# gt-jtx-2560.net
KiCad netlist of a schematic drawn in EAGLE
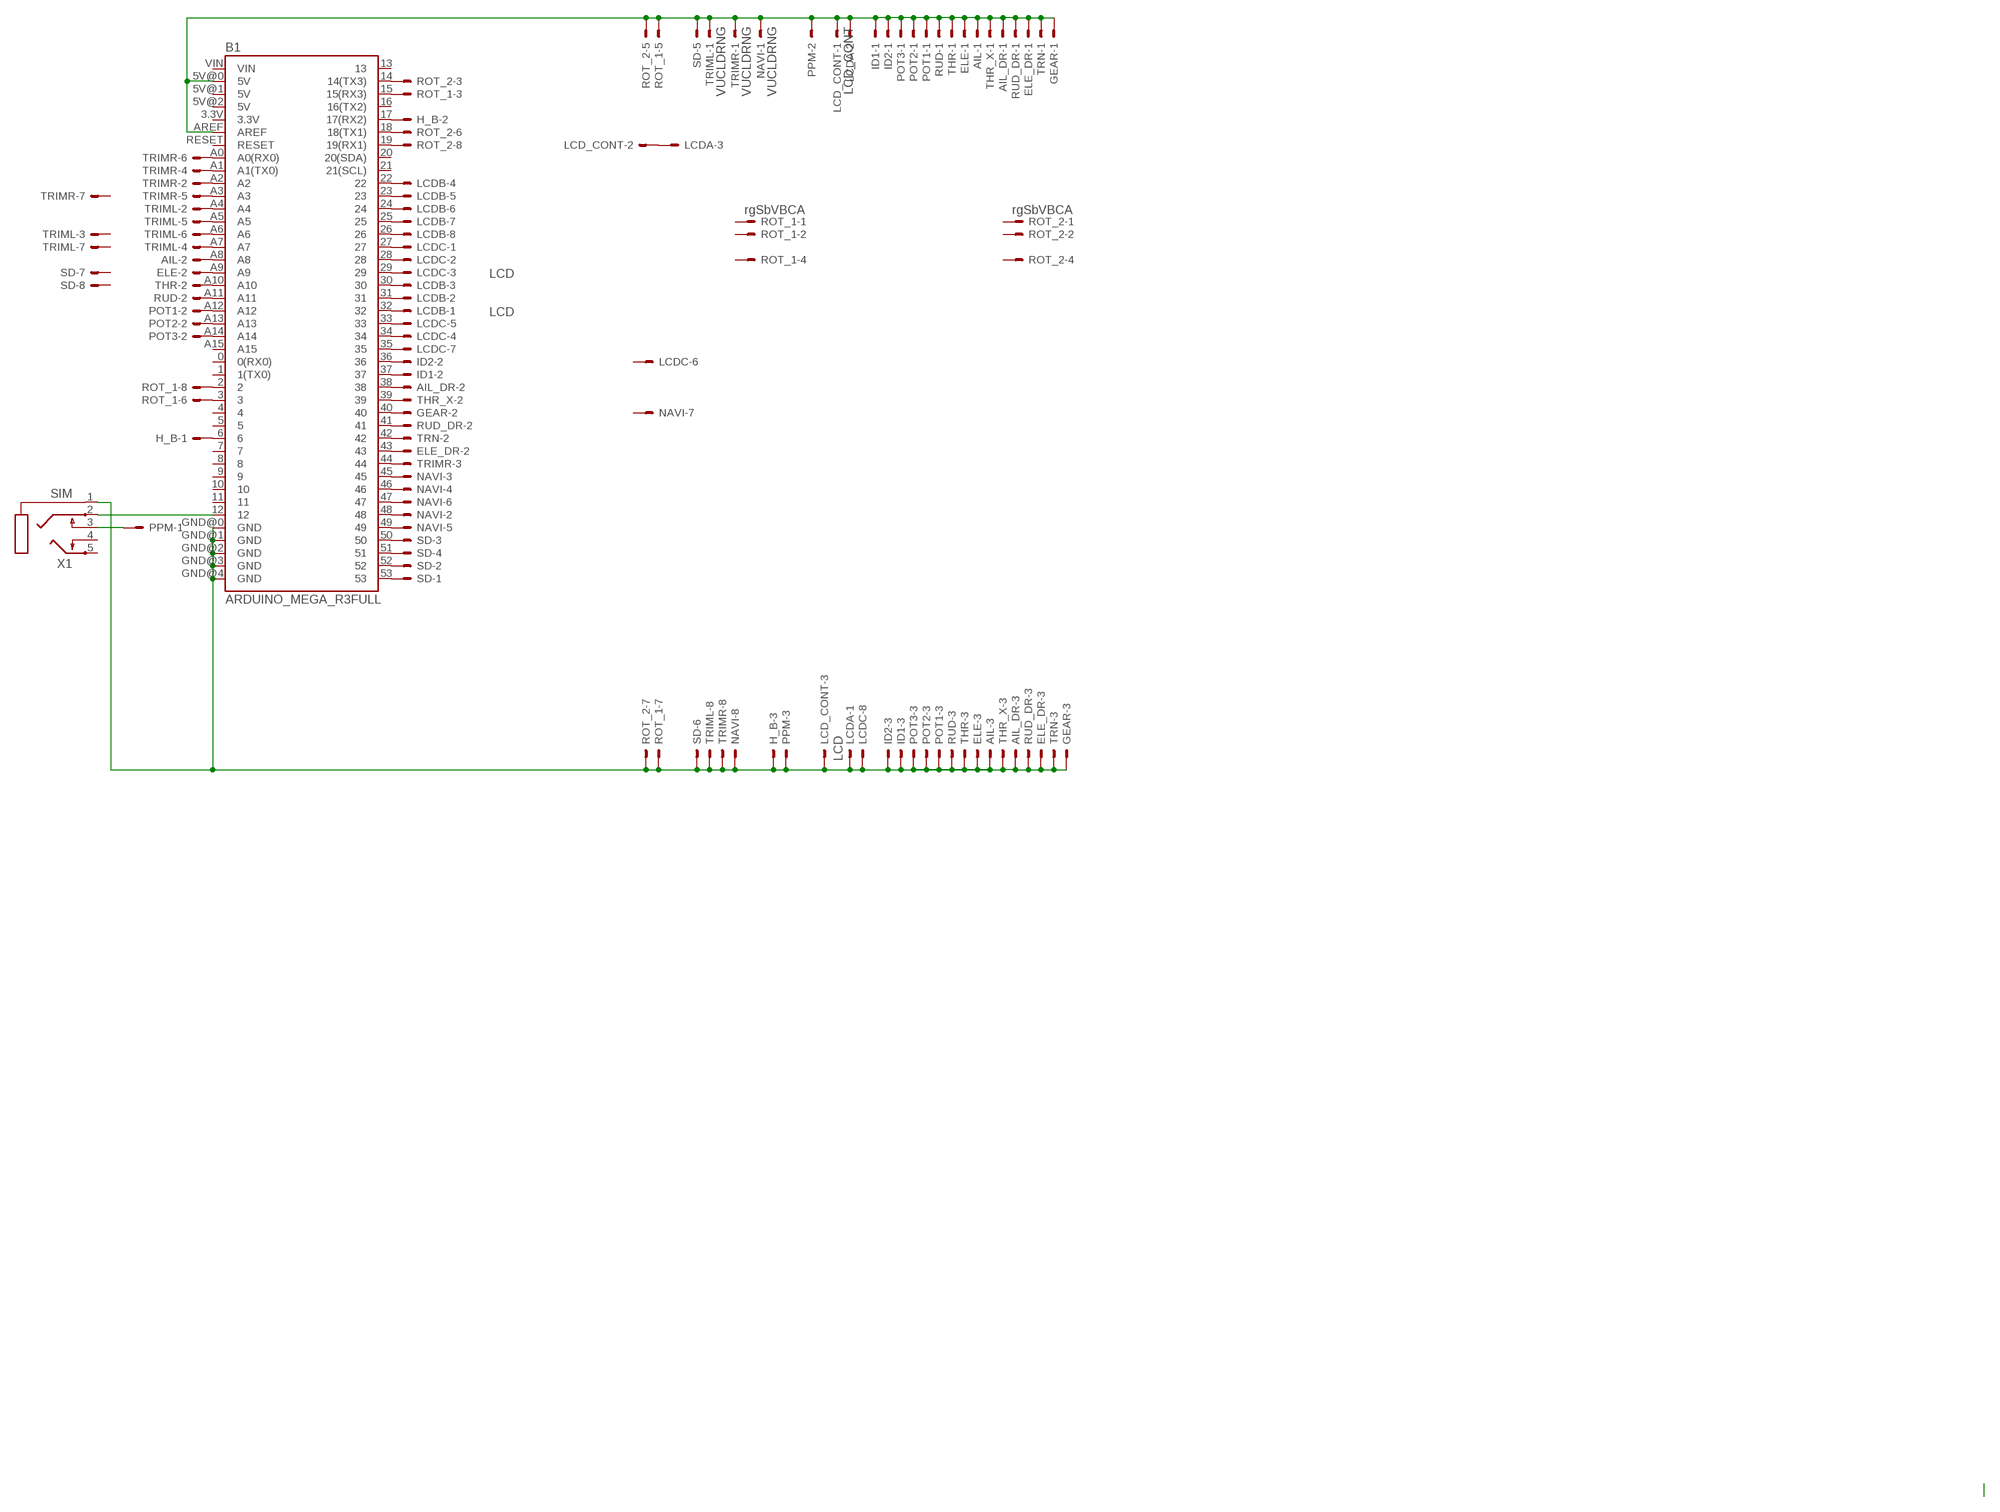
[diagram p0: schematic, sheet 1]

(export (version "E")
  (design (tool "Eeschema 10.0.6"))
  (components
    (comp (ref "AIL")
      (value "JST-XH-03-PIN-LONG-PAD")
      (footprint "eagle-import:JST-XH-03-PACKAGE-LONG-PAD")
      (libsource (lib "eagle-import") (part "JST-XH-03-PIN-LONG-PAD"))
    )
    (comp (ref "AIL_DR")
      (value "JST-XH-03-PIN-LONG-PAD")
      (footprint "eagle-import:JST-XH-03-PACKAGE-LONG-PAD")
      (libsource (lib "eagle-import") (part "JST-XH-03-PIN-LONG-PAD"))
    )
    (comp (ref "B1")
      (value "ARDUINO_MEGA_R3FULL")
      (footprint "eagle-import:ARDUINO_MEGA")
      (libsource (lib "eagle-import") (part "ARDUINO_MEGA_R3FULL"))
    )
    (comp (ref "ELE")
      (value "JST-XH-03-PIN-LONG-PAD")
      (footprint "eagle-import:JST-XH-03-PACKAGE-LONG-PAD")
      (libsource (lib "eagle-import") (part "JST-XH-03-PIN-LONG-PAD"))
    )
    (comp (ref "ELE_DR")
      (value "JST-XH-03-PIN-LONG-PAD")
      (footprint "eagle-import:JST-XH-03-PACKAGE-LONG-PAD")
      (libsource (lib "eagle-import") (part "JST-XH-03-PIN-LONG-PAD"))
    )
    (comp (ref "GEAR")
      (value "JST-XH-03-PIN-LONG-PAD")
      (footprint "eagle-import:JST-XH-03-PACKAGE-LONG-PAD")
      (libsource (lib "eagle-import") (part "JST-XH-03-PIN-LONG-PAD"))
    )
    (comp (ref "H_B")
      (value "JST-XH-03-PIN-LONG-PAD")
      (footprint "eagle-import:JST-XH-03-PACKAGE-LONG-PAD")
      (libsource (lib "eagle-import") (part "JST-XH-03-PIN-LONG-PAD"))
    )
    (comp (ref "ID1")
      (value "JST-XH-03-PIN-LONG-PAD")
      (footprint "eagle-import:JST-XH-03-PACKAGE-LONG-PAD")
      (libsource (lib "eagle-import") (part "JST-XH-03-PIN-LONG-PAD"))
    )
    (comp (ref "ID2")
      (value "JST-XH-03-PIN-LONG-PAD")
      (footprint "eagle-import:JST-XH-03-PACKAGE-LONG-PAD")
      (libsource (lib "eagle-import") (part "JST-XH-03-PIN-LONG-PAD"))
    )
    (comp (ref "LCDA")
      (value "LCD")
      (footprint "eagle-import:JST-XH-03-PACKAGE-LONG-PAD")
      (libsource (lib "eagle-import") (part "JST-XH-03-PIN-LONG-PAD"))
    )
    (comp (ref "LCDB")
      (value "LCD")
      (footprint "eagle-import:JST-XH-08-PACKAGE-LONG-PAD")
      (libsource (lib "eagle-import") (part "JST-XH-08-PIN-LONG-PAD"))
    )
    (comp (ref "LCDC")
      (value "LCD")
      (footprint "eagle-import:JST-XH-08-PACKAGE-LONG-PAD")
      (libsource (lib "eagle-import") (part "JST-XH-08-PIN-LONG-PAD"))
    )
    (comp (ref "LCD_CONT")
      (value "LCD_CONT")
      (footprint "eagle-import:JST-XH-03-PACKAGE-LONG-PAD")
      (libsource (lib "eagle-import") (part "JST-XH-03-PIN-LONG-PAD"))
    )
    (comp (ref "NAVI")
      (value "VUCLDRNG")
      (footprint "eagle-import:JST-XH-08-PACKAGE-LONG-PAD")
      (libsource (lib "eagle-import") (part "JST-XH-08-PIN-LONG-PAD"))
    )
    (comp (ref "POT1")
      (value "JST-XH-03-PIN-LONG-PAD")
      (footprint "eagle-import:JST-XH-03-PACKAGE-LONG-PAD")
      (libsource (lib "eagle-import") (part "JST-XH-03-PIN-LONG-PAD"))
    )
    (comp (ref "POT2")
      (value "JST-XH-03-PIN-LONG-PAD")
      (footprint "eagle-import:JST-XH-03-PACKAGE-LONG-PAD")
      (libsource (lib "eagle-import") (part "JST-XH-03-PIN-LONG-PAD"))
    )
    (comp (ref "POT3")
      (value "JST-XH-03-PIN-LONG-PAD")
      (footprint "eagle-import:JST-XH-03-PACKAGE-LONG-PAD")
      (libsource (lib "eagle-import") (part "JST-XH-03-PIN-LONG-PAD"))
    )
    (comp (ref "PPM")
      (value "JST-XH-03-PIN-LONG-PAD")
      (footprint "eagle-import:JST-XH-03-PACKAGE-LONG-PAD")
      (libsource (lib "eagle-import") (part "JST-XH-03-PIN-LONG-PAD"))
    )
    (comp (ref "ROT_1")
      (value "rgSbVBCA")
      (footprint "eagle-import:JST-XH-08-PACKAGE-LONG-PAD")
      (libsource (lib "eagle-import") (part "JST-XH-08-PIN-LONG-PAD"))
    )
    (comp (ref "ROT_2")
      (value "rgSbVBCA")
      (footprint "eagle-import:JST-XH-08-PACKAGE-LONG-PAD")
      (libsource (lib "eagle-import") (part "JST-XH-08-PIN-LONG-PAD"))
    )
    (comp (ref "RUD")
      (value "JST-XH-03-PIN-LONG-PAD")
      (footprint "eagle-import:JST-XH-03-PACKAGE-LONG-PAD")
      (libsource (lib "eagle-import") (part "JST-XH-03-PIN-LONG-PAD"))
    )
    (comp (ref "RUD_DR")
      (value "JST-XH-03-PIN-LONG-PAD")
      (footprint "eagle-import:JST-XH-03-PACKAGE-LONG-PAD")
      (libsource (lib "eagle-import") (part "JST-XH-03-PIN-LONG-PAD"))
    )
    (comp (ref "SD")
      (value "JST-XH-08-PIN-LONG-PAD")
      (footprint "eagle-import:JST-XH-08-PACKAGE-LONG-PAD")
      (libsource (lib "eagle-import") (part "JST-XH-08-PIN-LONG-PAD"))
    )
    (comp (ref "THR")
      (value "JST-XH-03-PIN-LONG-PAD")
      (footprint "eagle-import:JST-XH-03-PACKAGE-LONG-PAD")
      (libsource (lib "eagle-import") (part "JST-XH-03-PIN-LONG-PAD"))
    )
    (comp (ref "THR_X")
      (value "JST-XH-03-PIN-LONG-PAD")
      (footprint "eagle-import:JST-XH-03-PACKAGE-LONG-PAD")
      (libsource (lib "eagle-import") (part "JST-XH-03-PIN-LONG-PAD"))
    )
    (comp (ref "TRIML")
      (value "VUCLDRNG")
      (footprint "eagle-import:JST-XH-08-PACKAGE-LONG-PAD")
      (libsource (lib "eagle-import") (part "JST-XH-08-PIN-LONG-PAD"))
    )
    (comp (ref "TRIMR")
      (value "VUCLDRNG")
      (footprint "eagle-import:JST-XH-08-PACKAGE-LONG-PAD")
      (libsource (lib "eagle-import") (part "JST-XH-08-PIN-LONG-PAD"))
    )
    (comp (ref "TRN")
      (value "JST-XH-03-PIN-LONG-PAD")
      (footprint "eagle-import:JST-XH-03-PACKAGE-LONG-PAD")
      (libsource (lib "eagle-import") (part "JST-XH-03-PIN-LONG-PAD"))
    )
    (comp (ref "X1")
      (value "SIM")
      (footprint "eagle-import:STX3100")
      (libsource (lib "eagle-import") (part "STEREOJACK"))
    )
  )
  (nets
    (net (code "1") (name "Net-(AILA-S)") (class "Default")
      (node (ref "AIL") (pin "1") (pinfunction "S_1") (pintype "passive"))
      (node (ref "AIL_DR") (pin "1") (pinfunction "S_1") (pintype "passive"))
      (node (ref "B1") (pin "5V@0") (pinfunction "5V_5V@0") (pintype "bidirectional"))
      (node (ref "B1") (pin "AREF") (pinfunction "AREF_AREF") (pintype "bidirectional"))
      (node (ref "ELE") (pin "1") (pinfunction "S_1") (pintype "passive"))
      (node (ref "ELE_DR") (pin "1") (pinfunction "S_1") (pintype "passive"))
      (node (ref "GEAR") (pin "1") (pinfunction "S_1") (pintype "passive"))
      (node (ref "ID1") (pin "1") (pinfunction "S_1") (pintype "passive"))
      (node (ref "ID2") (pin "1") (pinfunction "S_1") (pintype "passive"))
      (node (ref "LCDA") (pin "2") (pinfunction "S_2") (pintype "passive"))
      (node (ref "LCD_CONT") (pin "1") (pinfunction "S_1") (pintype "passive"))
      (node (ref "NAVI") (pin "1") (pinfunction "S_1") (pintype "passive"))
      (node (ref "POT1") (pin "1") (pinfunction "S_1") (pintype "passive"))
      (node (ref "POT2") (pin "1") (pinfunction "S_1") (pintype "passive"))
      (node (ref "POT3") (pin "1") (pinfunction "S_1") (pintype "passive"))
      (node (ref "PPM") (pin "2") (pinfunction "S_2") (pintype "passive"))
      (node (ref "ROT_1") (pin "5") (pinfunction "S_5") (pintype "passive"))
      (node (ref "ROT_2") (pin "5") (pinfunction "S_5") (pintype "passive"))
      (node (ref "RUD") (pin "1") (pinfunction "S_1") (pintype "passive"))
      (node (ref "RUD_DR") (pin "1") (pinfunction "S_1") (pintype "passive"))
      (node (ref "SD") (pin "5") (pinfunction "S_5") (pintype "passive"))
      (node (ref "THR") (pin "1") (pinfunction "S_1") (pintype "passive"))
      (node (ref "THR_X") (pin "1") (pinfunction "S_1") (pintype "passive"))
      (node (ref "TRIML") (pin "1") (pinfunction "S_1") (pintype "passive"))
      (node (ref "TRIMR") (pin "1") (pinfunction "S_1") (pintype "passive"))
      (node (ref "TRN") (pin "1") (pinfunction "S_1") (pintype "passive"))
    )
    (net (code "2") (name "Net-(AILB-S)") (class "Default")
      (node (ref "AIL") (pin "2") (pinfunction "S_2") (pintype "passive"))
      (node (ref "B1") (pin "A8") (pinfunction "A8_A8") (pintype "bidirectional"))
    )
    (net (code "3") (name "Net-(AILC-S)") (class "Default")
      (node (ref "AIL") (pin "3") (pinfunction "S_3") (pintype "passive"))
      (node (ref "AIL_DR") (pin "3") (pinfunction "S_3") (pintype "passive"))
      (node (ref "B1") (pin "GND@0") (pinfunction "GND_GND@0") (pintype "bidirectional"))
      (node (ref "B1") (pin "GND@1") (pinfunction "GND_GND@1") (pintype "bidirectional"))
      (node (ref "B1") (pin "GND@2") (pinfunction "GND_GND@2") (pintype "bidirectional"))
      (node (ref "B1") (pin "GND@3") (pinfunction "GND_GND@3") (pintype "bidirectional"))
      (node (ref "B1") (pin "GND@4") (pinfunction "GND_GND@4") (pintype "bidirectional"))
      (node (ref "ELE") (pin "3") (pinfunction "S_3") (pintype "passive"))
      (node (ref "ELE_DR") (pin "3") (pinfunction "S_3") (pintype "passive"))
      (node (ref "GEAR") (pin "3") (pinfunction "S_3") (pintype "passive"))
      (node (ref "H_B") (pin "3") (pinfunction "S_3") (pintype "passive"))
      (node (ref "ID1") (pin "3") (pinfunction "S_3") (pintype "passive"))
      (node (ref "ID2") (pin "3") (pinfunction "S_3") (pintype "passive"))
      (node (ref "LCDA") (pin "1") (pinfunction "S_1") (pintype "passive"))
      (node (ref "LCDC") (pin "8") (pinfunction "S_8") (pintype "passive"))
      (node (ref "LCD_CONT") (pin "3") (pinfunction "S_3") (pintype "passive"))
      (node (ref "NAVI") (pin "8") (pinfunction "S_8") (pintype "passive"))
      (node (ref "POT1") (pin "3") (pinfunction "S_3") (pintype "passive"))
      (node (ref "POT2") (pin "3") (pinfunction "S_3") (pintype "passive"))
      (node (ref "POT3") (pin "3") (pinfunction "S_3") (pintype "passive"))
      (node (ref "PPM") (pin "3") (pinfunction "S_3") (pintype "passive"))
      (node (ref "ROT_1") (pin "7") (pinfunction "S_7") (pintype "passive"))
      (node (ref "ROT_2") (pin "7") (pinfunction "S_7") (pintype "passive"))
      (node (ref "RUD") (pin "3") (pinfunction "S_3") (pintype "passive"))
      (node (ref "RUD_DR") (pin "3") (pinfunction "S_3") (pintype "passive"))
      (node (ref "SD") (pin "6") (pinfunction "S_6") (pintype "passive"))
      (node (ref "THR") (pin "3") (pinfunction "S_3") (pintype "passive"))
      (node (ref "THR_X") (pin "3") (pinfunction "S_3") (pintype "passive"))
      (node (ref "TRIML") (pin "8") (pinfunction "S_8") (pintype "passive"))
      (node (ref "TRIMR") (pin "8") (pinfunction "S_8") (pintype "passive"))
      (node (ref "TRN") (pin "3") (pinfunction "S_3") (pintype "passive"))
      (node (ref "X1") (pin "1") (pinfunction "1_1") (pintype "passive"))
    )
    (net (code "4") (name "Net-(AIL_DRB-S)") (class "Default")
      (node (ref "AIL_DR") (pin "2") (pinfunction "S_2") (pintype "passive"))
      (node (ref "B1") (pin "38") (pinfunction "38_38") (pintype "bidirectional"))
    )
    (net (code "5") (name "Net-(B1-14(TX3))") (class "Default")
      (node (ref "B1") (pin "14") (pinfunction "14(TX3)_14") (pintype "bidirectional"))
      (node (ref "ROT_2") (pin "3") (pinfunction "S_3") (pintype "passive"))
    )
    (net (code "6") (name "Net-(B1-15(RX3))") (class "Default")
      (node (ref "B1") (pin "15") (pinfunction "15(RX3)_15") (pintype "bidirectional"))
      (node (ref "ROT_1") (pin "3") (pinfunction "S_3") (pintype "passive"))
    )
    (net (code "7") (name "Net-(B1-17(RX2))") (class "Default")
      (node (ref "B1") (pin "17") (pinfunction "17(RX2)_17") (pintype "bidirectional"))
      (node (ref "H_B") (pin "2") (pinfunction "S_2") (pintype "passive"))
    )
    (net (code "8") (name "Net-(B1-18(TX1))") (class "Default")
      (node (ref "B1") (pin "18") (pinfunction "18(TX1)_18") (pintype "bidirectional"))
      (node (ref "ROT_2") (pin "6") (pinfunction "S_6") (pintype "passive"))
    )
    (net (code "9") (name "Net-(B1-19(RX1))") (class "Default")
      (node (ref "B1") (pin "19") (pinfunction "19(RX1)_19") (pintype "bidirectional"))
      (node (ref "ROT_2") (pin "8") (pinfunction "S_8") (pintype "passive"))
    )
    (net (code "10") (name "Net-(B1-A0(RX0))") (class "Default")
      (node (ref "B1") (pin "A0") (pinfunction "A0(RX0)_A0") (pintype "bidirectional"))
      (node (ref "TRIMR") (pin "6") (pinfunction "S_6") (pintype "passive"))
    )
    (net (code "11") (name "Net-(B1-A1(TX0))") (class "Default")
      (node (ref "B1") (pin "A1") (pinfunction "A1(TX0)_A1") (pintype "bidirectional"))
      (node (ref "TRIMR") (pin "4") (pinfunction "S_4") (pintype "passive"))
    )
    (net (code "12") (name "Net-(B1-Pad12)") (class "Default")
      (node (ref "B1") (pin "12") (pinfunction "12_12") (pintype "bidirectional"))
      (node (ref "X1") (pin "2") (pinfunction "2_2") (pintype "passive"))
    )
    (net (code "13") (name "Net-(ELEB-S)") (class "Default")
      (node (ref "B1") (pin "A9") (pinfunction "A9_A9") (pintype "bidirectional"))
      (node (ref "ELE") (pin "2") (pinfunction "S_2") (pintype "passive"))
    )
    (net (code "14") (name "Net-(ELE_DRB-S)") (class "Default")
      (node (ref "B1") (pin "43") (pinfunction "43_43") (pintype "bidirectional"))
      (node (ref "ELE_DR") (pin "2") (pinfunction "S_2") (pintype "passive"))
    )
    (net (code "15") (name "Net-(GEARB-S)") (class "Default")
      (node (ref "B1") (pin "40") (pinfunction "40_40") (pintype "bidirectional"))
      (node (ref "GEAR") (pin "2") (pinfunction "S_2") (pintype "passive"))
    )
    (net (code "16") (name "Net-(H_BA-S)") (class "Default")
      (node (ref "B1") (pin "6") (pinfunction "6_6") (pintype "bidirectional"))
      (node (ref "H_B") (pin "1") (pinfunction "S_1") (pintype "passive"))
    )
    (net (code "17") (name "Net-(ID1B-S)") (class "Default")
      (node (ref "B1") (pin "37") (pinfunction "37_37") (pintype "bidirectional"))
      (node (ref "ID1") (pin "2") (pinfunction "S_2") (pintype "passive"))
    )
    (net (code "18") (name "Net-(ID2B-S)") (class "Default")
      (node (ref "B1") (pin "36") (pinfunction "36_36") (pintype "bidirectional"))
      (node (ref "ID2") (pin "2") (pinfunction "S_2") (pintype "passive"))
    )
    (net (code "19") (name "Net-(LCDAC-S)") (class "Default")
      (node (ref "LCDA") (pin "3") (pinfunction "S_3") (pintype "passive"))
      (node (ref "LCD_CONT") (pin "2") (pinfunction "S_2") (pintype "passive"))
    )
    (net (code "20") (name "Net-(LCDBA-S)") (class "Default")
      (node (ref "B1") (pin "32") (pinfunction "32_32") (pintype "bidirectional"))
      (node (ref "LCDB") (pin "1") (pinfunction "S_1") (pintype "passive"))
    )
    (net (code "21") (name "Net-(LCDBB-S)") (class "Default")
      (node (ref "B1") (pin "31") (pinfunction "31_31") (pintype "bidirectional"))
      (node (ref "LCDB") (pin "2") (pinfunction "S_2") (pintype "passive"))
    )
    (net (code "22") (name "Net-(LCDBC-S)") (class "Default")
      (node (ref "B1") (pin "30") (pinfunction "30_30") (pintype "bidirectional"))
      (node (ref "LCDB") (pin "3") (pinfunction "S_3") (pintype "passive"))
    )
    (net (code "23") (name "Net-(LCDBD-S)") (class "Default")
      (node (ref "B1") (pin "22") (pinfunction "22_22") (pintype "bidirectional"))
      (node (ref "LCDB") (pin "4") (pinfunction "S_4") (pintype "passive"))
    )
    (net (code "24") (name "Net-(LCDBE-S)") (class "Default")
      (node (ref "B1") (pin "23") (pinfunction "23_23") (pintype "bidirectional"))
      (node (ref "LCDB") (pin "5") (pinfunction "S_5") (pintype "passive"))
    )
    (net (code "25") (name "Net-(LCDBF-S)") (class "Default")
      (node (ref "B1") (pin "24") (pinfunction "24_24") (pintype "bidirectional"))
      (node (ref "LCDB") (pin "6") (pinfunction "S_6") (pintype "passive"))
    )
    (net (code "26") (name "Net-(LCDBG-S)") (class "Default")
      (node (ref "B1") (pin "25") (pinfunction "25_25") (pintype "bidirectional"))
      (node (ref "LCDB") (pin "7") (pinfunction "S_7") (pintype "passive"))
    )
    (net (code "27") (name "Net-(LCDBH-S)") (class "Default")
      (node (ref "B1") (pin "26") (pinfunction "26_26") (pintype "bidirectional"))
      (node (ref "LCDB") (pin "8") (pinfunction "S_8") (pintype "passive"))
    )
    (net (code "28") (name "Net-(LCDCA-S)") (class "Default")
      (node (ref "B1") (pin "27") (pinfunction "27_27") (pintype "bidirectional"))
      (node (ref "LCDC") (pin "1") (pinfunction "S_1") (pintype "passive"))
    )
    (net (code "29") (name "Net-(LCDCB-S)") (class "Default")
      (node (ref "B1") (pin "28") (pinfunction "28_28") (pintype "bidirectional"))
      (node (ref "LCDC") (pin "2") (pinfunction "S_2") (pintype "passive"))
    )
    (net (code "30") (name "Net-(LCDCC-S)") (class "Default")
      (node (ref "B1") (pin "29") (pinfunction "29_29") (pintype "bidirectional"))
      (node (ref "LCDC") (pin "3") (pinfunction "S_3") (pintype "passive"))
    )
    (net (code "31") (name "Net-(LCDCD-S)") (class "Default")
      (node (ref "B1") (pin "34") (pinfunction "34_34") (pintype "bidirectional"))
      (node (ref "LCDC") (pin "4") (pinfunction "S_4") (pintype "passive"))
    )
    (net (code "32") (name "Net-(LCDCE-S)") (class "Default")
      (node (ref "B1") (pin "33") (pinfunction "33_33") (pintype "bidirectional"))
      (node (ref "LCDC") (pin "5") (pinfunction "S_5") (pintype "passive"))
    )
    (net (code "33") (name "Net-(LCDCG-S)") (class "Default")
      (node (ref "B1") (pin "35") (pinfunction "35_35") (pintype "bidirectional"))
      (node (ref "LCDC") (pin "7") (pinfunction "S_7") (pintype "passive"))
    )
    (net (code "34") (name "Net-(NAVIB-S)") (class "Default")
      (node (ref "B1") (pin "48") (pinfunction "48_48") (pintype "bidirectional"))
      (node (ref "NAVI") (pin "2") (pinfunction "S_2") (pintype "passive"))
    )
    (net (code "35") (name "Net-(NAVIC-S)") (class "Default")
      (node (ref "B1") (pin "45") (pinfunction "45_45") (pintype "bidirectional"))
      (node (ref "NAVI") (pin "3") (pinfunction "S_3") (pintype "passive"))
    )
    (net (code "36") (name "Net-(NAVID-S)") (class "Default")
      (node (ref "B1") (pin "46") (pinfunction "46_46") (pintype "bidirectional"))
      (node (ref "NAVI") (pin "4") (pinfunction "S_4") (pintype "passive"))
    )
    (net (code "37") (name "Net-(NAVIE-S)") (class "Default")
      (node (ref "B1") (pin "49") (pinfunction "49_49") (pintype "bidirectional"))
      (node (ref "NAVI") (pin "5") (pinfunction "S_5") (pintype "passive"))
    )
    (net (code "38") (name "Net-(NAVIF-S)") (class "Default")
      (node (ref "B1") (pin "47") (pinfunction "47_47") (pintype "bidirectional"))
      (node (ref "NAVI") (pin "6") (pinfunction "S_6") (pintype "passive"))
    )
    (net (code "39") (name "Net-(POT1B-S)") (class "Default")
      (node (ref "B1") (pin "A12") (pinfunction "A12_A12") (pintype "bidirectional"))
      (node (ref "POT1") (pin "2") (pinfunction "S_2") (pintype "passive"))
    )
    (net (code "40") (name "Net-(POT2B-S)") (class "Default")
      (node (ref "B1") (pin "A13") (pinfunction "A13_A13") (pintype "bidirectional"))
      (node (ref "POT2") (pin "2") (pinfunction "S_2") (pintype "passive"))
    )
    (net (code "41") (name "Net-(POT3B-S)") (class "Default")
      (node (ref "B1") (pin "A14") (pinfunction "A14_A14") (pintype "bidirectional"))
      (node (ref "POT3") (pin "2") (pinfunction "S_2") (pintype "passive"))
    )
    (net (code "42") (name "Net-(PPMA-S)") (class "Default")
      (node (ref "PPM") (pin "1") (pinfunction "S_1") (pintype "passive"))
      (node (ref "X1") (pin "3") (pinfunction "3_3") (pintype "passive"))
    )
    (net (code "43") (name "Net-(ROT_1F-S)") (class "Default")
      (node (ref "B1") (pin "3") (pinfunction "3_3") (pintype "bidirectional"))
      (node (ref "ROT_1") (pin "6") (pinfunction "S_6") (pintype "passive"))
    )
    (net (code "44") (name "Net-(ROT_1H-S)") (class "Default")
      (node (ref "B1") (pin "2") (pinfunction "2_2") (pintype "bidirectional"))
      (node (ref "ROT_1") (pin "8") (pinfunction "S_8") (pintype "passive"))
    )
    (net (code "45") (name "Net-(RUDB-S)") (class "Default")
      (node (ref "B1") (pin "A11") (pinfunction "A11_A11") (pintype "bidirectional"))
      (node (ref "RUD") (pin "2") (pinfunction "S_2") (pintype "passive"))
    )
    (net (code "46") (name "Net-(RUD_DRB-S)") (class "Default")
      (node (ref "B1") (pin "41") (pinfunction "41_41") (pintype "bidirectional"))
      (node (ref "RUD_DR") (pin "2") (pinfunction "S_2") (pintype "passive"))
    )
    (net (code "47") (name "Net-(SDA-S)") (class "Default")
      (node (ref "B1") (pin "53") (pinfunction "53_53") (pintype "bidirectional"))
      (node (ref "SD") (pin "1") (pinfunction "S_1") (pintype "passive"))
    )
    (net (code "48") (name "Net-(SDB-S)") (class "Default")
      (node (ref "B1") (pin "52") (pinfunction "52_52") (pintype "bidirectional"))
      (node (ref "SD") (pin "2") (pinfunction "S_2") (pintype "passive"))
    )
    (net (code "49") (name "Net-(SDC-S)") (class "Default")
      (node (ref "B1") (pin "50") (pinfunction "50_50") (pintype "bidirectional"))
      (node (ref "SD") (pin "3") (pinfunction "S_3") (pintype "passive"))
    )
    (net (code "50") (name "Net-(SDD-S)") (class "Default")
      (node (ref "B1") (pin "51") (pinfunction "51_51") (pintype "bidirectional"))
      (node (ref "SD") (pin "4") (pinfunction "S_4") (pintype "passive"))
    )
    (net (code "51") (name "Net-(THRB-S)") (class "Default")
      (node (ref "B1") (pin "A10") (pinfunction "A10_A10") (pintype "bidirectional"))
      (node (ref "THR") (pin "2") (pinfunction "S_2") (pintype "passive"))
    )
    (net (code "52") (name "Net-(THR_XB-S)") (class "Default")
      (node (ref "B1") (pin "39") (pinfunction "39_39") (pintype "bidirectional"))
      (node (ref "THR_X") (pin "2") (pinfunction "S_2") (pintype "passive"))
    )
    (net (code "53") (name "Net-(TRIMLB-S)") (class "Default")
      (node (ref "B1") (pin "A4") (pinfunction "A4_A4") (pintype "bidirectional"))
      (node (ref "TRIML") (pin "2") (pinfunction "S_2") (pintype "passive"))
    )
    (net (code "54") (name "Net-(TRIMLD-S)") (class "Default")
      (node (ref "B1") (pin "A7") (pinfunction "A7_A7") (pintype "bidirectional"))
      (node (ref "TRIML") (pin "4") (pinfunction "S_4") (pintype "passive"))
    )
    (net (code "55") (name "Net-(TRIMLE-S)") (class "Default")
      (node (ref "B1") (pin "A5") (pinfunction "A5_A5") (pintype "bidirectional"))
      (node (ref "TRIML") (pin "5") (pinfunction "S_5") (pintype "passive"))
    )
    (net (code "56") (name "Net-(TRIMLF-S)") (class "Default")
      (node (ref "B1") (pin "A6") (pinfunction "A6_A6") (pintype "bidirectional"))
      (node (ref "TRIML") (pin "6") (pinfunction "S_6") (pintype "passive"))
    )
    (net (code "57") (name "Net-(TRIMRB-S)") (class "Default")
      (node (ref "B1") (pin "A2") (pinfunction "A2_A2") (pintype "bidirectional"))
      (node (ref "TRIMR") (pin "2") (pinfunction "S_2") (pintype "passive"))
    )
    (net (code "58") (name "Net-(TRIMRC-S)") (class "Default")
      (node (ref "B1") (pin "44") (pinfunction "44_44") (pintype "bidirectional"))
      (node (ref "TRIMR") (pin "3") (pinfunction "S_3") (pintype "passive"))
    )
    (net (code "59") (name "Net-(TRIMRE-S)") (class "Default")
      (node (ref "B1") (pin "A3") (pinfunction "A3_A3") (pintype "bidirectional"))
      (node (ref "TRIMR") (pin "5") (pinfunction "S_5") (pintype "passive"))
    )
    (net (code "60") (name "Net-(TRNB-S)") (class "Default")
      (node (ref "B1") (pin "42") (pinfunction "42_42") (pintype "bidirectional"))
      (node (ref "TRN") (pin "2") (pinfunction "S_2") (pintype "passive"))
    )
    (net (code "61") (name "unconnected-(B1-0(RX0)-Pad0)") (class "Default")
      (node (ref "B1") (pin "0") (pinfunction "0(RX0)_0") (pintype "bidirectional"))
    )
    (net (code "62") (name "unconnected-(B1-1(TX0)-Pad1)") (class "Default")
      (node (ref "B1") (pin "1") (pinfunction "1(TX0)_1") (pintype "bidirectional"))
    )
    (net (code "63") (name "unconnected-(B1-5V-Pad5V@1)") (class "Default")
      (node (ref "B1") (pin "5V@1") (pinfunction "5V_5V@1") (pintype "bidirectional"))
    )
    (net (code "64") (name "unconnected-(B1-5V-Pad5V@2)") (class "Default")
      (node (ref "B1") (pin "5V@2") (pinfunction "5V_5V@2") (pintype "bidirectional"))
    )
    (net (code "65") (name "unconnected-(B1-16(TX2)-Pad16)") (class "Default")
      (node (ref "B1") (pin "16") (pinfunction "16(TX2)_16") (pintype "bidirectional"))
    )
    (net (code "66") (name "unconnected-(B1-20(SDA)-Pad20)") (class "Default")
      (node (ref "B1") (pin "20") (pinfunction "20(SDA)_20") (pintype "bidirectional"))
    )
    (net (code "67") (name "unconnected-(B1-21(SCL)-Pad21)") (class "Default")
      (node (ref "B1") (pin "21") (pinfunction "21(SCL)_21") (pintype "bidirectional"))
    )
    (net (code "68") (name "unconnected-(B1-Pad3.3V)") (class "Default")
      (node (ref "B1") (pin "3.3V") (pinfunction "3.3V_3.3V") (pintype "bidirectional"))
    )
    (net (code "69") (name "unconnected-(B1-Pad4)") (class "Default")
      (node (ref "B1") (pin "4") (pinfunction "4_4") (pintype "bidirectional"))
    )
    (net (code "70") (name "unconnected-(B1-Pad5)") (class "Default")
      (node (ref "B1") (pin "5") (pinfunction "5_5") (pintype "bidirectional"))
    )
    (net (code "71") (name "unconnected-(B1-Pad7)") (class "Default")
      (node (ref "B1") (pin "7") (pinfunction "7_7") (pintype "bidirectional"))
    )
    (net (code "72") (name "unconnected-(B1-Pad8)") (class "Default")
      (node (ref "B1") (pin "8") (pinfunction "8_8") (pintype "bidirectional"))
    )
    (net (code "73") (name "unconnected-(B1-Pad9)") (class "Default")
      (node (ref "B1") (pin "9") (pinfunction "9_9") (pintype "bidirectional"))
    )
    (net (code "74") (name "unconnected-(B1-Pad10)") (class "Default")
      (node (ref "B1") (pin "10") (pinfunction "10_10") (pintype "bidirectional"))
    )
    (net (code "75") (name "unconnected-(B1-Pad11)") (class "Default")
      (node (ref "B1") (pin "11") (pinfunction "11_11") (pintype "bidirectional"))
    )
    (net (code "76") (name "unconnected-(B1-Pad13)") (class "Default")
      (node (ref "B1") (pin "13") (pinfunction "13_13") (pintype "bidirectional"))
    )
    (net (code "77") (name "unconnected-(B1-PadA15)") (class "Default")
      (node (ref "B1") (pin "A15") (pinfunction "A15_A15") (pintype "bidirectional"))
    )
    (net (code "78") (name "unconnected-(B1-PadRESET)") (class "Default")
      (node (ref "B1") (pin "RESET") (pinfunction "RESET_RESET") (pintype "bidirectional"))
    )
    (net (code "79") (name "unconnected-(B1-PadVIN)") (class "Default")
      (node (ref "B1") (pin "VIN") (pinfunction "VIN_VIN") (pintype "bidirectional"))
    )
    (net (code "80") (name "unconnected-(LCDCF-S-Pad6)") (class "Default")
      (node (ref "LCDC") (pin "6") (pinfunction "S_6") (pintype "passive"))
    )
    (net (code "81") (name "unconnected-(NAVIG-S-Pad7)") (class "Default")
      (node (ref "NAVI") (pin "7") (pinfunction "S_7") (pintype "passive"))
    )
    (net (code "82") (name "unconnected-(ROT_1A-S-Pad1)") (class "Default")
      (node (ref "ROT_1") (pin "1") (pinfunction "S_1") (pintype "passive"))
    )
    (net (code "83") (name "unconnected-(ROT_1B-S-Pad2)") (class "Default")
      (node (ref "ROT_1") (pin "2") (pinfunction "S_2") (pintype "passive"))
    )
    (net (code "84") (name "unconnected-(ROT_1D-S-Pad4)") (class "Default")
      (node (ref "ROT_1") (pin "4") (pinfunction "S_4") (pintype "passive"))
    )
    (net (code "85") (name "unconnected-(ROT_2A-S-Pad1)") (class "Default")
      (node (ref "ROT_2") (pin "1") (pinfunction "S_1") (pintype "passive"))
    )
    (net (code "86") (name "unconnected-(ROT_2B-S-Pad2)") (class "Default")
      (node (ref "ROT_2") (pin "2") (pinfunction "S_2") (pintype "passive"))
    )
    (net (code "87") (name "unconnected-(ROT_2D-S-Pad4)") (class "Default")
      (node (ref "ROT_2") (pin "4") (pinfunction "S_4") (pintype "passive"))
    )
    (net (code "88") (name "unconnected-(SDG-S-Pad7)") (class "Default")
      (node (ref "SD") (pin "7") (pinfunction "S_7") (pintype "passive"))
    )
    (net (code "89") (name "unconnected-(SDH-S-Pad8)") (class "Default")
      (node (ref "SD") (pin "8") (pinfunction "S_8") (pintype "passive"))
    )
    (net (code "90") (name "unconnected-(TRIMLC-S-Pad3)") (class "Default")
      (node (ref "TRIML") (pin "3") (pinfunction "S_3") (pintype "passive"))
    )
    (net (code "91") (name "unconnected-(TRIMLG-S-Pad7)") (class "Default")
      (node (ref "TRIML") (pin "7") (pinfunction "S_7") (pintype "passive"))
    )
    (net (code "92") (name "unconnected-(TRIMRG-S-Pad7)") (class "Default")
      (node (ref "TRIMR") (pin "7") (pinfunction "S_7") (pintype "passive"))
    )
    (net (code "93") (name "unconnected-(X1-Pad4)") (class "Default")
      (node (ref "X1") (pin "4") (pinfunction "4_4") (pintype "passive"))
    )
    (net (code "94") (name "unconnected-(X1-Pad5)") (class "Default")
      (node (ref "X1") (pin "5") (pinfunction "5_5") (pintype "passive"))
    )
  )
)
